# Arduino_MEGA2560_ref.net
KiCad netlist of a schematic drawn in EAGLE
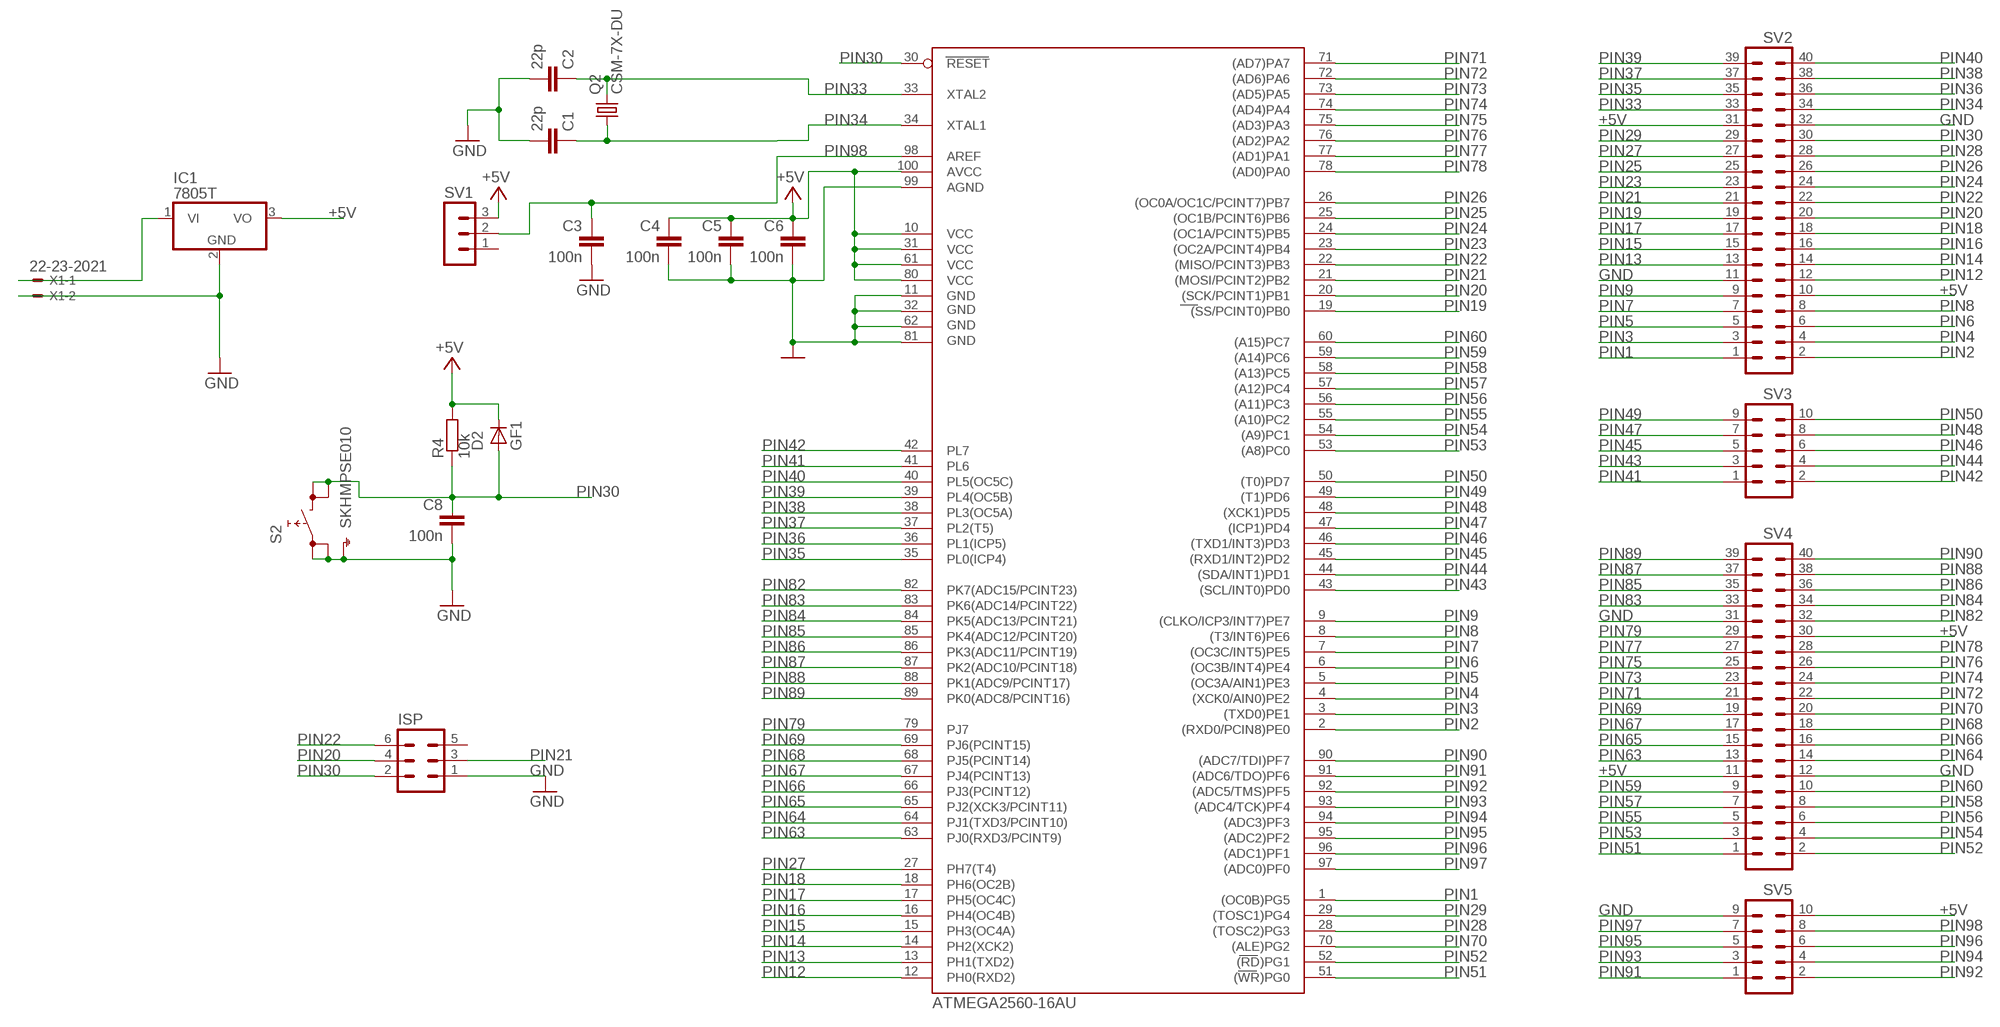
[diagram p0: schematic, sheet 1]

(export (version "E")
  (design (tool "Eeschema 10.0.6"))
  (components
    (comp (ref "C1")
      (value "22p")
      (footprint "eagle-import:C0603-ROUND")
      (libsource (lib "eagle-import") (part "C-EU0603-RND"))
    )
    (comp (ref "C2")
      (value "22p")
      (footprint "eagle-import:C0603-ROUND")
      (libsource (lib "eagle-import") (part "C-EU0603-RND"))
    )
    (comp (ref "C3")
      (value "100n")
      (footprint "eagle-import:C0603-ROUND")
      (libsource (lib "eagle-import") (part "C-EU0603-RND"))
    )
    (comp (ref "C4")
      (value "100n")
      (footprint "eagle-import:C0603-ROUND")
      (libsource (lib "eagle-import") (part "C-EU0603-RND"))
    )
    (comp (ref "C5")
      (value "100n")
      (footprint "eagle-import:C0603-ROUND")
      (libsource (lib "eagle-import") (part "C-EU0603-RND"))
    )
    (comp (ref "C6")
      (value "100n")
      (footprint "eagle-import:C0603-ROUND")
      (libsource (lib "eagle-import") (part "C-EU0603-RND"))
    )
    (comp (ref "C8")
      (value "100n")
      (footprint "eagle-import:C0603-ROUND")
      (libsource (lib "eagle-import") (part "C-EU0603-RND"))
    )
    (comp (ref "D2")
      (value "GF1")
      (footprint "eagle-import:SMA-DO214AC")
      (libsource (lib "eagle-import") (part "GF1"))
    )
    (comp (ref "IC1")
      (value "7805T")
      (footprint "eagle-import:TO220H")
      (libsource (lib "eagle-import") (part "78T05"))
    )
    (comp (ref "IC3")
      (value "ATMEGA2560-16AU")
      (footprint "eagle-import:TQFP100")
      (libsource (lib "eagle-import") (part "ATMEGAAU1280-16"))
    )
    (comp (ref "ISP")
      (value "MA03-2")
      (footprint "eagle-import:MA03-2")
      (libsource (lib "eagle-import") (part "MA03-2"))
    )
    (comp (ref "Q2")
      (value "CSM-7X-DU")
      (footprint "eagle-import:CSM-7X-DU")
      (libsource (lib "eagle-import") (part "CSM-7X-DU"))
    )
    (comp (ref "R4")
      (value "10k")
      (footprint "eagle-import:SMS-0")
      (libsource (lib "eagle-import") (part "SMS-0"))
    )
    (comp (ref "S2")
      (value "SKHMPSE010")
      (footprint "eagle-import:SKHMPXE010")
      (libsource (lib "eagle-import") (part "SKHMPE010S"))
    )
    (comp (ref "SV1")
      (value "MA03-1")
      (footprint "eagle-import:MA03-1")
      (libsource (lib "eagle-import") (part "MA03-1"))
    )
    (comp (ref "SV2")
      (value "MA20-2")
      (footprint "eagle-import:MA20-2")
      (libsource (lib "eagle-import") (part "MA20-2"))
    )
    (comp (ref "SV3")
      (value "MA05-2")
      (footprint "eagle-import:MA05-2")
      (libsource (lib "eagle-import") (part "MA05-2"))
    )
    (comp (ref "SV4")
      (value "MA20-2")
      (footprint "eagle-import:MA20-2")
      (libsource (lib "eagle-import") (part "MA20-2"))
    )
    (comp (ref "SV5")
      (value "MA05-2")
      (footprint "eagle-import:MA05-2")
      (libsource (lib "eagle-import") (part "MA05-2"))
    )
    (comp (ref "X1")
      (value "22-23-2021")
      (footprint "eagle-import:22-23-2021")
      (fields (field (name "MF") "MOLEX"))
      (libsource (lib "eagle-import") (part "22-23-2021"))
    )
  )
  (nets
    (net (code "1") (name "+5V") (class "Default")
      (node (ref "C4") (pin "1") (pinfunction "1_1") (pintype "passive"))
      (node (ref "C5") (pin "1") (pinfunction "1_1") (pintype "passive"))
      (node (ref "C6") (pin "1") (pinfunction "1_1") (pintype "passive"))
      (node (ref "D2") (pin "K") (pinfunction "C_K") (pintype "passive"))
      (node (ref "IC1") (pin "3") (pinfunction "VO_3") (pintype "passive"))
      (node (ref "IC3") (pin "10") (pinfunction "VCC_10") (pintype "power_in"))
      (node (ref "IC3") (pin "100") (pinfunction "AVCC_100") (pintype "power_in"))
      (node (ref "IC3") (pin "31") (pinfunction "VCC1_31") (pintype "power_in"))
      (node (ref "IC3") (pin "61") (pinfunction "VCC2_61") (pintype "power_in"))
      (node (ref "IC3") (pin "80") (pinfunction "VCC3_80") (pintype "power_in"))
      (node (ref "R4") (pin "1") (pinfunction "1_1") (pintype "passive"))
      (node (ref "SV1") (pin "3") (pinfunction "3_3") (pintype "passive"))
      (node (ref "SV2") (pin "10") (pinfunction "10_10") (pintype "passive"))
      (node (ref "SV2") (pin "31") (pinfunction "31_31") (pintype "passive"))
      (node (ref "SV4") (pin "11") (pinfunction "11_11") (pintype "passive"))
      (node (ref "SV4") (pin "30") (pinfunction "30_30") (pintype "passive"))
      (node (ref "SV5") (pin "10") (pinfunction "10_10") (pintype "passive"))
    )
    (net (code "2") (name "/PIN1") (class "Default")
      (node (ref "IC3") (pin "1") (pinfunction "(OC0B)PG5_1") (pintype "bidirectional"))
      (node (ref "SV2") (pin "1") (pinfunction "1_1") (pintype "passive"))
    )
    (net (code "3") (name "/PIN2") (class "Default")
      (node (ref "IC3") (pin "2") (pinfunction "(RXD0/PCIN8)PE0_2") (pintype "bidirectional"))
      (node (ref "SV2") (pin "2") (pinfunction "2_2") (pintype "passive"))
    )
    (net (code "4") (name "/PIN3") (class "Default")
      (node (ref "IC3") (pin "3") (pinfunction "(TXD0)PE1_3") (pintype "bidirectional"))
      (node (ref "SV2") (pin "3") (pinfunction "3_3") (pintype "passive"))
    )
    (net (code "5") (name "/PIN4") (class "Default")
      (node (ref "IC3") (pin "4") (pinfunction "(XCK0/AIN0)PE2_4") (pintype "bidirectional"))
      (node (ref "SV2") (pin "4") (pinfunction "4_4") (pintype "passive"))
    )
    (net (code "6") (name "/PIN5") (class "Default")
      (node (ref "IC3") (pin "5") (pinfunction "(OC3A/AIN1)PE3_5") (pintype "bidirectional"))
      (node (ref "SV2") (pin "5") (pinfunction "5_5") (pintype "passive"))
    )
    (net (code "7") (name "/PIN6") (class "Default")
      (node (ref "IC3") (pin "6") (pinfunction "(OC3B/INT4)PE4_6") (pintype "bidirectional"))
      (node (ref "SV2") (pin "6") (pinfunction "6_6") (pintype "passive"))
    )
    (net (code "8") (name "/PIN7") (class "Default")
      (node (ref "IC3") (pin "7") (pinfunction "(OC3C/INT5)PE5_7") (pintype "bidirectional"))
      (node (ref "SV2") (pin "7") (pinfunction "7_7") (pintype "passive"))
    )
    (net (code "9") (name "/PIN8") (class "Default")
      (node (ref "IC3") (pin "8") (pinfunction "(T3/INT6)PE6_8") (pintype "bidirectional"))
      (node (ref "SV2") (pin "8") (pinfunction "8_8") (pintype "passive"))
    )
    (net (code "10") (name "/PIN9") (class "Default")
      (node (ref "IC3") (pin "9") (pinfunction "(CLKO/ICP3/INT7)PE7_9") (pintype "bidirectional"))
      (node (ref "SV2") (pin "9") (pinfunction "9_9") (pintype "passive"))
    )
    (net (code "11") (name "/PIN12") (class "Default")
      (node (ref "IC3") (pin "12") (pinfunction "PH0(RXD2)_12") (pintype "bidirectional"))
      (node (ref "SV2") (pin "12") (pinfunction "12_12") (pintype "passive"))
    )
    (net (code "12") (name "/PIN13") (class "Default")
      (node (ref "IC3") (pin "13") (pinfunction "PH1(TXD2)_13") (pintype "bidirectional"))
      (node (ref "SV2") (pin "13") (pinfunction "13_13") (pintype "passive"))
    )
    (net (code "13") (name "/PIN14") (class "Default")
      (node (ref "IC3") (pin "14") (pinfunction "PH2(XCK2)_14") (pintype "bidirectional"))
      (node (ref "SV2") (pin "14") (pinfunction "14_14") (pintype "passive"))
    )
    (net (code "14") (name "/PIN15") (class "Default")
      (node (ref "IC3") (pin "15") (pinfunction "PH3(OC4A)_15") (pintype "bidirectional"))
      (node (ref "SV2") (pin "15") (pinfunction "15_15") (pintype "passive"))
    )
    (net (code "15") (name "/PIN16") (class "Default")
      (node (ref "IC3") (pin "16") (pinfunction "PH4(OC4B)_16") (pintype "bidirectional"))
      (node (ref "SV2") (pin "16") (pinfunction "16_16") (pintype "passive"))
    )
    (net (code "16") (name "/PIN17") (class "Default")
      (node (ref "IC3") (pin "17") (pinfunction "PH5(OC4C)_17") (pintype "bidirectional"))
      (node (ref "SV2") (pin "17") (pinfunction "17_17") (pintype "passive"))
    )
    (net (code "17") (name "/PIN18") (class "Default")
      (node (ref "IC3") (pin "18") (pinfunction "PH6(OC2B)_18") (pintype "bidirectional"))
      (node (ref "SV2") (pin "18") (pinfunction "18_18") (pintype "passive"))
    )
    (net (code "18") (name "/PIN19") (class "Default")
      (node (ref "IC3") (pin "19") (pinfunction "(SS/PCINT0)PB0_19") (pintype "bidirectional"))
      (node (ref "SV2") (pin "19") (pinfunction "19_19") (pintype "passive"))
    )
    (net (code "19") (name "/PIN20") (class "Default")
      (node (ref "IC3") (pin "20") (pinfunction "(SCK/PCINT1)PB1_20") (pintype "bidirectional"))
      (node (ref "ISP") (pin "4") (pinfunction "4_4") (pintype "passive"))
      (node (ref "SV2") (pin "20") (pinfunction "20_20") (pintype "passive"))
    )
    (net (code "20") (name "/PIN21") (class "Default")
      (node (ref "IC3") (pin "21") (pinfunction "(MOSI/PCINT2)PB2_21") (pintype "bidirectional"))
      (node (ref "ISP") (pin "3") (pinfunction "3_3") (pintype "passive"))
      (node (ref "SV2") (pin "21") (pinfunction "21_21") (pintype "passive"))
    )
    (net (code "21") (name "/PIN22") (class "Default")
      (node (ref "IC3") (pin "22") (pinfunction "(MISO/PCINT3)PB3_22") (pintype "bidirectional"))
      (node (ref "ISP") (pin "6") (pinfunction "6_6") (pintype "passive"))
      (node (ref "SV2") (pin "22") (pinfunction "22_22") (pintype "passive"))
    )
    (net (code "22") (name "/PIN23") (class "Default")
      (node (ref "IC3") (pin "23") (pinfunction "(OC2A/PCINT4)PB4_23") (pintype "bidirectional"))
      (node (ref "SV2") (pin "23") (pinfunction "23_23") (pintype "passive"))
    )
    (net (code "23") (name "/PIN24") (class "Default")
      (node (ref "IC3") (pin "24") (pinfunction "(OC1A/PCINT5)PB5_24") (pintype "bidirectional"))
      (node (ref "SV2") (pin "24") (pinfunction "24_24") (pintype "passive"))
    )
    (net (code "24") (name "/PIN25") (class "Default")
      (node (ref "IC3") (pin "25") (pinfunction "(OC1B/PCINT6)PB6_25") (pintype "bidirectional"))
      (node (ref "SV2") (pin "25") (pinfunction "25_25") (pintype "passive"))
    )
    (net (code "25") (name "/PIN26") (class "Default")
      (node (ref "IC3") (pin "26") (pinfunction "(OC0A/OC1C/PCINT7)PB7_26") (pintype "bidirectional"))
      (node (ref "SV2") (pin "26") (pinfunction "26_26") (pintype "passive"))
    )
    (net (code "26") (name "/PIN27") (class "Default")
      (node (ref "IC3") (pin "27") (pinfunction "PH7(T4)_27") (pintype "bidirectional"))
      (node (ref "SV2") (pin "27") (pinfunction "27_27") (pintype "passive"))
    )
    (net (code "27") (name "/PIN28") (class "Default")
      (node (ref "IC3") (pin "28") (pinfunction "(TOSC2)PG3_28") (pintype "bidirectional"))
      (node (ref "SV2") (pin "28") (pinfunction "28_28") (pintype "passive"))
    )
    (net (code "28") (name "/PIN29") (class "Default")
      (node (ref "IC3") (pin "29") (pinfunction "(TOSC1)PG4_29") (pintype "bidirectional"))
      (node (ref "SV2") (pin "29") (pinfunction "29_29") (pintype "passive"))
    )
    (net (code "29") (name "/PIN30") (class "Default")
      (node (ref "C8") (pin "1") (pinfunction "1_1") (pintype "passive"))
      (node (ref "D2") (pin "A") (pinfunction "A_A") (pintype "passive"))
      (node (ref "IC3") (pin "30") (pinfunction "RESET_30") (pintype "input"))
      (node (ref "ISP") (pin "2") (pinfunction "2_2") (pintype "passive"))
      (node (ref "R4") (pin "2") (pinfunction "2_2") (pintype "passive"))
      (node (ref "S2") (pin "3") (pinfunction "2.1_3") (pintype "passive"))
      (node (ref "S2") (pin "4") (pinfunction "2.2_4") (pintype "passive"))
      (node (ref "SV2") (pin "30") (pinfunction "30_30") (pintype "passive"))
    )
    (net (code "30") (name "/PIN33") (class "Default")
      (node (ref "C2") (pin "1") (pinfunction "1_1") (pintype "passive"))
      (node (ref "IC3") (pin "33") (pinfunction "XTAL2_33") (pintype "output"))
      (node (ref "Q2") (pin "2") (pinfunction "2_2") (pintype "passive"))
      (node (ref "SV2") (pin "33") (pinfunction "33_33") (pintype "passive"))
    )
    (net (code "31") (name "/PIN34") (class "Default")
      (node (ref "C1") (pin "1") (pinfunction "1_1") (pintype "passive"))
      (node (ref "IC3") (pin "34") (pinfunction "XTAL1_34") (pintype "input"))
      (node (ref "Q2") (pin "1") (pinfunction "1_1") (pintype "passive"))
      (node (ref "SV2") (pin "34") (pinfunction "34_34") (pintype "passive"))
    )
    (net (code "32") (name "/PIN35") (class "Default")
      (node (ref "IC3") (pin "35") (pinfunction "PL0(ICP4)_35") (pintype "bidirectional"))
      (node (ref "SV2") (pin "35") (pinfunction "35_35") (pintype "passive"))
    )
    (net (code "33") (name "/PIN36") (class "Default")
      (node (ref "IC3") (pin "36") (pinfunction "PL1(ICP5)_36") (pintype "bidirectional"))
      (node (ref "SV2") (pin "36") (pinfunction "36_36") (pintype "passive"))
    )
    (net (code "34") (name "/PIN37") (class "Default")
      (node (ref "IC3") (pin "37") (pinfunction "PL2(T5)_37") (pintype "bidirectional"))
      (node (ref "SV2") (pin "37") (pinfunction "37_37") (pintype "passive"))
    )
    (net (code "35") (name "/PIN38") (class "Default")
      (node (ref "IC3") (pin "38") (pinfunction "PL3(OC5A)_38") (pintype "bidirectional"))
      (node (ref "SV2") (pin "38") (pinfunction "38_38") (pintype "passive"))
    )
    (net (code "36") (name "/PIN39") (class "Default")
      (node (ref "IC3") (pin "39") (pinfunction "PL4(OC5B)_39") (pintype "bidirectional"))
      (node (ref "SV2") (pin "39") (pinfunction "39_39") (pintype "passive"))
    )
    (net (code "37") (name "/PIN40") (class "Default")
      (node (ref "IC3") (pin "40") (pinfunction "PL5(OC5C)_40") (pintype "bidirectional"))
      (node (ref "SV2") (pin "40") (pinfunction "40_40") (pintype "passive"))
    )
    (net (code "38") (name "/PIN41") (class "Default")
      (node (ref "IC3") (pin "41") (pinfunction "PL6_41") (pintype "bidirectional"))
      (node (ref "SV3") (pin "1") (pinfunction "1_1") (pintype "passive"))
    )
    (net (code "39") (name "/PIN42") (class "Default")
      (node (ref "IC3") (pin "42") (pinfunction "PL7_42") (pintype "bidirectional"))
      (node (ref "SV3") (pin "2") (pinfunction "2_2") (pintype "passive"))
    )
    (net (code "40") (name "/PIN43") (class "Default")
      (node (ref "IC3") (pin "43") (pinfunction "(SCL/INT0)PD0_43") (pintype "bidirectional"))
      (node (ref "SV3") (pin "3") (pinfunction "3_3") (pintype "passive"))
    )
    (net (code "41") (name "/PIN44") (class "Default")
      (node (ref "IC3") (pin "44") (pinfunction "(SDA/INT1)PD1_44") (pintype "bidirectional"))
      (node (ref "SV3") (pin "4") (pinfunction "4_4") (pintype "passive"))
    )
    (net (code "42") (name "/PIN45") (class "Default")
      (node (ref "IC3") (pin "45") (pinfunction "(RXD1/INT2)PD2_45") (pintype "bidirectional"))
      (node (ref "SV3") (pin "5") (pinfunction "5_5") (pintype "passive"))
    )
    (net (code "43") (name "/PIN46") (class "Default")
      (node (ref "IC3") (pin "46") (pinfunction "(TXD1/INT3)PD3_46") (pintype "bidirectional"))
      (node (ref "SV3") (pin "6") (pinfunction "6_6") (pintype "passive"))
    )
    (net (code "44") (name "/PIN47") (class "Default")
      (node (ref "IC3") (pin "47") (pinfunction "(ICP1)PD4_47") (pintype "bidirectional"))
      (node (ref "SV3") (pin "7") (pinfunction "7_7") (pintype "passive"))
    )
    (net (code "45") (name "/PIN48") (class "Default")
      (node (ref "IC3") (pin "48") (pinfunction "(XCK1)PD5_48") (pintype "bidirectional"))
      (node (ref "SV3") (pin "8") (pinfunction "8_8") (pintype "passive"))
    )
    (net (code "46") (name "/PIN49") (class "Default")
      (node (ref "IC3") (pin "49") (pinfunction "(T1)PD6_49") (pintype "bidirectional"))
      (node (ref "SV3") (pin "9") (pinfunction "9_9") (pintype "passive"))
    )
    (net (code "47") (name "/PIN50") (class "Default")
      (node (ref "IC3") (pin "50") (pinfunction "(T0)PD7_50") (pintype "bidirectional"))
      (node (ref "SV3") (pin "10") (pinfunction "10_10") (pintype "passive"))
    )
    (net (code "48") (name "/PIN51") (class "Default")
      (node (ref "IC3") (pin "51") (pinfunction "(WR)PG0_51") (pintype "bidirectional"))
      (node (ref "SV4") (pin "1") (pinfunction "1_1") (pintype "passive"))
    )
    (net (code "49") (name "/PIN52") (class "Default")
      (node (ref "IC3") (pin "52") (pinfunction "(RD)PG1_52") (pintype "bidirectional"))
      (node (ref "SV4") (pin "2") (pinfunction "2_2") (pintype "passive"))
    )
    (net (code "50") (name "/PIN53") (class "Default")
      (node (ref "IC3") (pin "53") (pinfunction "(A8)PC0_53") (pintype "bidirectional"))
      (node (ref "SV4") (pin "3") (pinfunction "3_3") (pintype "passive"))
    )
    (net (code "51") (name "/PIN54") (class "Default")
      (node (ref "IC3") (pin "54") (pinfunction "(A9)PC1_54") (pintype "bidirectional"))
      (node (ref "SV4") (pin "4") (pinfunction "4_4") (pintype "passive"))
    )
    (net (code "52") (name "/PIN55") (class "Default")
      (node (ref "IC3") (pin "55") (pinfunction "(A10)PC2_55") (pintype "bidirectional"))
      (node (ref "SV4") (pin "5") (pinfunction "5_5") (pintype "passive"))
    )
    (net (code "53") (name "/PIN56") (class "Default")
      (node (ref "IC3") (pin "56") (pinfunction "(A11)PC3_56") (pintype "bidirectional"))
      (node (ref "SV4") (pin "6") (pinfunction "6_6") (pintype "passive"))
    )
    (net (code "54") (name "/PIN57") (class "Default")
      (node (ref "IC3") (pin "57") (pinfunction "(A12)PC4_57") (pintype "bidirectional"))
      (node (ref "SV4") (pin "7") (pinfunction "7_7") (pintype "passive"))
    )
    (net (code "55") (name "/PIN58") (class "Default")
      (node (ref "IC3") (pin "58") (pinfunction "(A13)PC5_58") (pintype "bidirectional"))
      (node (ref "SV4") (pin "8") (pinfunction "8_8") (pintype "passive"))
    )
    (net (code "56") (name "/PIN59") (class "Default")
      (node (ref "IC3") (pin "59") (pinfunction "(A14)PC6_59") (pintype "bidirectional"))
      (node (ref "SV4") (pin "9") (pinfunction "9_9") (pintype "passive"))
    )
    (net (code "57") (name "/PIN60") (class "Default")
      (node (ref "IC3") (pin "60") (pinfunction "(A15)PC7_60") (pintype "bidirectional"))
      (node (ref "SV4") (pin "10") (pinfunction "10_10") (pintype "passive"))
    )
    (net (code "58") (name "/PIN63") (class "Default")
      (node (ref "IC3") (pin "63") (pinfunction "PJ0(RXD3/PCINT9)_63") (pintype "bidirectional"))
      (node (ref "SV4") (pin "13") (pinfunction "13_13") (pintype "passive"))
    )
    (net (code "59") (name "/PIN64") (class "Default")
      (node (ref "IC3") (pin "64") (pinfunction "PJ1(TXD3/PCINT10)_64") (pintype "bidirectional"))
      (node (ref "SV4") (pin "14") (pinfunction "14_14") (pintype "passive"))
    )
    (net (code "60") (name "/PIN65") (class "Default")
      (node (ref "IC3") (pin "65") (pinfunction "PJ2(XCK3/PCINT11)_65") (pintype "bidirectional"))
      (node (ref "SV4") (pin "15") (pinfunction "15_15") (pintype "passive"))
    )
    (net (code "61") (name "/PIN66") (class "Default")
      (node (ref "IC3") (pin "66") (pinfunction "PJ3(PCINT12)_66") (pintype "bidirectional"))
      (node (ref "SV4") (pin "16") (pinfunction "16_16") (pintype "passive"))
    )
    (net (code "62") (name "/PIN67") (class "Default")
      (node (ref "IC3") (pin "67") (pinfunction "PJ4(PCINT13)_67") (pintype "bidirectional"))
      (node (ref "SV4") (pin "17") (pinfunction "17_17") (pintype "passive"))
    )
    (net (code "63") (name "/PIN68") (class "Default")
      (node (ref "IC3") (pin "68") (pinfunction "PJ5(PCINT14)_68") (pintype "bidirectional"))
      (node (ref "SV4") (pin "18") (pinfunction "18_18") (pintype "passive"))
    )
    (net (code "64") (name "/PIN69") (class "Default")
      (node (ref "IC3") (pin "69") (pinfunction "PJ6(PCINT15)_69") (pintype "bidirectional"))
      (node (ref "SV4") (pin "19") (pinfunction "19_19") (pintype "passive"))
    )
    (net (code "65") (name "/PIN70") (class "Default")
      (node (ref "IC3") (pin "70") (pinfunction "(ALE)PG2_70") (pintype "bidirectional"))
      (node (ref "SV4") (pin "20") (pinfunction "20_20") (pintype "passive"))
    )
    (net (code "66") (name "/PIN71") (class "Default")
      (node (ref "IC3") (pin "71") (pinfunction "(AD7)PA7_71") (pintype "bidirectional"))
      (node (ref "SV4") (pin "21") (pinfunction "21_21") (pintype "passive"))
    )
    (net (code "67") (name "/PIN72") (class "Default")
      (node (ref "IC3") (pin "72") (pinfunction "(AD6)PA6_72") (pintype "bidirectional"))
      (node (ref "SV4") (pin "22") (pinfunction "22_22") (pintype "passive"))
    )
    (net (code "68") (name "/PIN73") (class "Default")
      (node (ref "IC3") (pin "73") (pinfunction "(AD5)PA5_73") (pintype "bidirectional"))
      (node (ref "SV4") (pin "23") (pinfunction "23_23") (pintype "passive"))
    )
    (net (code "69") (name "/PIN74") (class "Default")
      (node (ref "IC3") (pin "74") (pinfunction "(AD4)PA4_74") (pintype "bidirectional"))
      (node (ref "SV4") (pin "24") (pinfunction "24_24") (pintype "passive"))
    )
    (net (code "70") (name "/PIN75") (class "Default")
      (node (ref "IC3") (pin "75") (pinfunction "(AD3)PA3_75") (pintype "bidirectional"))
      (node (ref "SV4") (pin "25") (pinfunction "25_25") (pintype "passive"))
    )
    (net (code "71") (name "/PIN76") (class "Default")
      (node (ref "IC3") (pin "76") (pinfunction "(AD2)PA2_76") (pintype "bidirectional"))
      (node (ref "SV4") (pin "26") (pinfunction "26_26") (pintype "passive"))
    )
    (net (code "72") (name "/PIN77") (class "Default")
      (node (ref "IC3") (pin "77") (pinfunction "(AD1)PA1_77") (pintype "bidirectional"))
      (node (ref "SV4") (pin "27") (pinfunction "27_27") (pintype "passive"))
    )
    (net (code "73") (name "/PIN78") (class "Default")
      (node (ref "IC3") (pin "78") (pinfunction "(AD0)PA0_78") (pintype "bidirectional"))
      (node (ref "SV4") (pin "28") (pinfunction "28_28") (pintype "passive"))
    )
    (net (code "74") (name "/PIN79") (class "Default")
      (node (ref "IC3") (pin "79") (pinfunction "PJ7_79") (pintype "bidirectional"))
      (node (ref "SV4") (pin "29") (pinfunction "29_29") (pintype "passive"))
    )
    (net (code "75") (name "/PIN82") (class "Default")
      (node (ref "IC3") (pin "82") (pinfunction "PK7(ADC15/PCINT23)_82") (pintype "bidirectional"))
      (node (ref "SV4") (pin "32") (pinfunction "32_32") (pintype "passive"))
    )
    (net (code "76") (name "/PIN83") (class "Default")
      (node (ref "IC3") (pin "83") (pinfunction "PK6(ADC14/PCINT22)_83") (pintype "bidirectional"))
      (node (ref "SV4") (pin "33") (pinfunction "33_33") (pintype "passive"))
    )
    (net (code "77") (name "/PIN84") (class "Default")
      (node (ref "IC3") (pin "84") (pinfunction "PK5(ADC13/PCINT21)_84") (pintype "bidirectional"))
      (node (ref "SV4") (pin "34") (pinfunction "34_34") (pintype "passive"))
    )
    (net (code "78") (name "/PIN85") (class "Default")
      (node (ref "IC3") (pin "85") (pinfunction "PK4(ADC12/PCINT20)_85") (pintype "bidirectional"))
      (node (ref "SV4") (pin "35") (pinfunction "35_35") (pintype "passive"))
    )
    (net (code "79") (name "/PIN86") (class "Default")
      (node (ref "IC3") (pin "86") (pinfunction "PK3(ADC11/PCINT19)_86") (pintype "bidirectional"))
      (node (ref "SV4") (pin "36") (pinfunction "36_36") (pintype "passive"))
    )
    (net (code "80") (name "/PIN87") (class "Default")
      (node (ref "IC3") (pin "87") (pinfunction "PK2(ADC10/PCINT18)_87") (pintype "bidirectional"))
      (node (ref "SV4") (pin "37") (pinfunction "37_37") (pintype "passive"))
    )
    (net (code "81") (name "/PIN88") (class "Default")
      (node (ref "IC3") (pin "88") (pinfunction "PK1(ADC9/PCINT17)_88") (pintype "bidirectional"))
      (node (ref "SV4") (pin "38") (pinfunction "38_38") (pintype "passive"))
    )
    (net (code "82") (name "/PIN89") (class "Default")
      (node (ref "IC3") (pin "89") (pinfunction "PK0(ADC8/PCINT16)_89") (pintype "bidirectional"))
      (node (ref "SV4") (pin "39") (pinfunction "39_39") (pintype "passive"))
    )
    (net (code "83") (name "/PIN90") (class "Default")
      (node (ref "IC3") (pin "90") (pinfunction "(ADC7/TDI)PF7_90") (pintype "bidirectional"))
      (node (ref "SV4") (pin "40") (pinfunction "40_40") (pintype "passive"))
    )
    (net (code "84") (name "/PIN91") (class "Default")
      (node (ref "IC3") (pin "91") (pinfunction "(ADC6/TDO)PF6_91") (pintype "bidirectional"))
      (node (ref "SV5") (pin "1") (pinfunction "1_1") (pintype "passive"))
    )
    (net (code "85") (name "/PIN92") (class "Default")
      (node (ref "IC3") (pin "92") (pinfunction "(ADC5/TMS)PF5_92") (pintype "bidirectional"))
      (node (ref "SV5") (pin "2") (pinfunction "2_2") (pintype "passive"))
    )
    (net (code "86") (name "/PIN93") (class "Default")
      (node (ref "IC3") (pin "93") (pinfunction "(ADC4/TCK)PF4_93") (pintype "bidirectional"))
      (node (ref "SV5") (pin "3") (pinfunction "3_3") (pintype "passive"))
    )
    (net (code "87") (name "/PIN94") (class "Default")
      (node (ref "IC3") (pin "94") (pinfunction "(ADC3)PF3_94") (pintype "bidirectional"))
      (node (ref "SV5") (pin "4") (pinfunction "4_4") (pintype "passive"))
    )
    (net (code "88") (name "/PIN95") (class "Default")
      (node (ref "IC3") (pin "95") (pinfunction "(ADC2)PF2_95") (pintype "bidirectional"))
      (node (ref "SV5") (pin "5") (pinfunction "5_5") (pintype "passive"))
    )
    (net (code "89") (name "/PIN96") (class "Default")
      (node (ref "IC3") (pin "96") (pinfunction "(ADC1)PF1_96") (pintype "bidirectional"))
      (node (ref "SV5") (pin "6") (pinfunction "6_6") (pintype "passive"))
    )
    (net (code "90") (name "/PIN97") (class "Default")
      (node (ref "IC3") (pin "97") (pinfunction "(ADC0)PF0_97") (pintype "bidirectional"))
      (node (ref "SV5") (pin "7") (pinfunction "7_7") (pintype "passive"))
    )
    (net (code "91") (name "/PIN98") (class "Default")
      (node (ref "C3") (pin "1") (pinfunction "1_1") (pintype "passive"))
      (node (ref "IC3") (pin "98") (pinfunction "AREF_98") (pintype "bidirectional"))
      (node (ref "SV1") (pin "2") (pinfunction "2_2") (pintype "passive"))
      (node (ref "SV5") (pin "8") (pinfunction "8_8") (pintype "passive"))
    )
    (net (code "92") (name "GND") (class "Default")
      (node (ref "C1") (pin "2") (pinfunction "2_2") (pintype "passive"))
      (node (ref "C2") (pin "2") (pinfunction "2_2") (pintype "passive"))
      (node (ref "C3") (pin "2") (pinfunction "2_2") (pintype "passive"))
      (node (ref "C4") (pin "2") (pinfunction "2_2") (pintype "passive"))
      (node (ref "C5") (pin "2") (pinfunction "2_2") (pintype "passive"))
      (node (ref "C6") (pin "2") (pinfunction "2_2") (pintype "passive"))
      (node (ref "C8") (pin "2") (pinfunction "2_2") (pintype "passive"))
      (node (ref "IC1") (pin "2") (pinfunction "GND_2") (pintype "passive"))
      (node (ref "IC3") (pin "11") (pinfunction "GND_11") (pintype "power_in"))
      (node (ref "IC3") (pin "32") (pinfunction "GND1_32") (pintype "power_in"))
      (node (ref "IC3") (pin "62") (pinfunction "GND2_62") (pintype "power_in"))
      (node (ref "IC3") (pin "81") (pinfunction "GND3_81") (pintype "power_in"))
      (node (ref "IC3") (pin "99") (pinfunction "AGND_99") (pintype "power_in"))
      (node (ref "ISP") (pin "1") (pinfunction "1_1") (pintype "passive"))
      (node (ref "S2") (pin "1") (pinfunction "1.1_1") (pintype "passive"))
      (node (ref "S2") (pin "2") (pinfunction "1.2_2") (pintype "passive"))
      (node (ref "S2") (pin "5") (pinfunction "SH_5") (pintype "passive"))
      (node (ref "SV2") (pin "11") (pinfunction "11_11") (pintype "passive"))
      (node (ref "SV2") (pin "32") (pinfunction "32_32") (pintype "passive"))
      (node (ref "SV4") (pin "12") (pinfunction "12_12") (pintype "passive"))
      (node (ref "SV4") (pin "31") (pinfunction "31_31") (pintype "passive"))
      (node (ref "SV5") (pin "9") (pinfunction "9_9") (pintype "passive"))
      (node (ref "X1") (pin "2") (pinfunction "S_2") (pintype "passive"))
    )
    (net (code "93") (name "Net-(IC1-VI)") (class "Default")
      (node (ref "IC1") (pin "1") (pinfunction "VI_1") (pintype "input"))
      (node (ref "X1") (pin "1") (pinfunction "S_1") (pintype "passive"))
    )
    (net (code "94") (name "unconnected-(ISP-Pad5)") (class "Default")
      (node (ref "ISP") (pin "5") (pinfunction "5_5") (pintype "passive"))
    )
    (net (code "95") (name "unconnected-(SV1-Pad1)") (class "Default")
      (node (ref "SV1") (pin "1") (pinfunction "1_1") (pintype "passive"))
    )
  )
)
